# PHY.net
KiCad netlist of a schematic drawn in Altium Designer
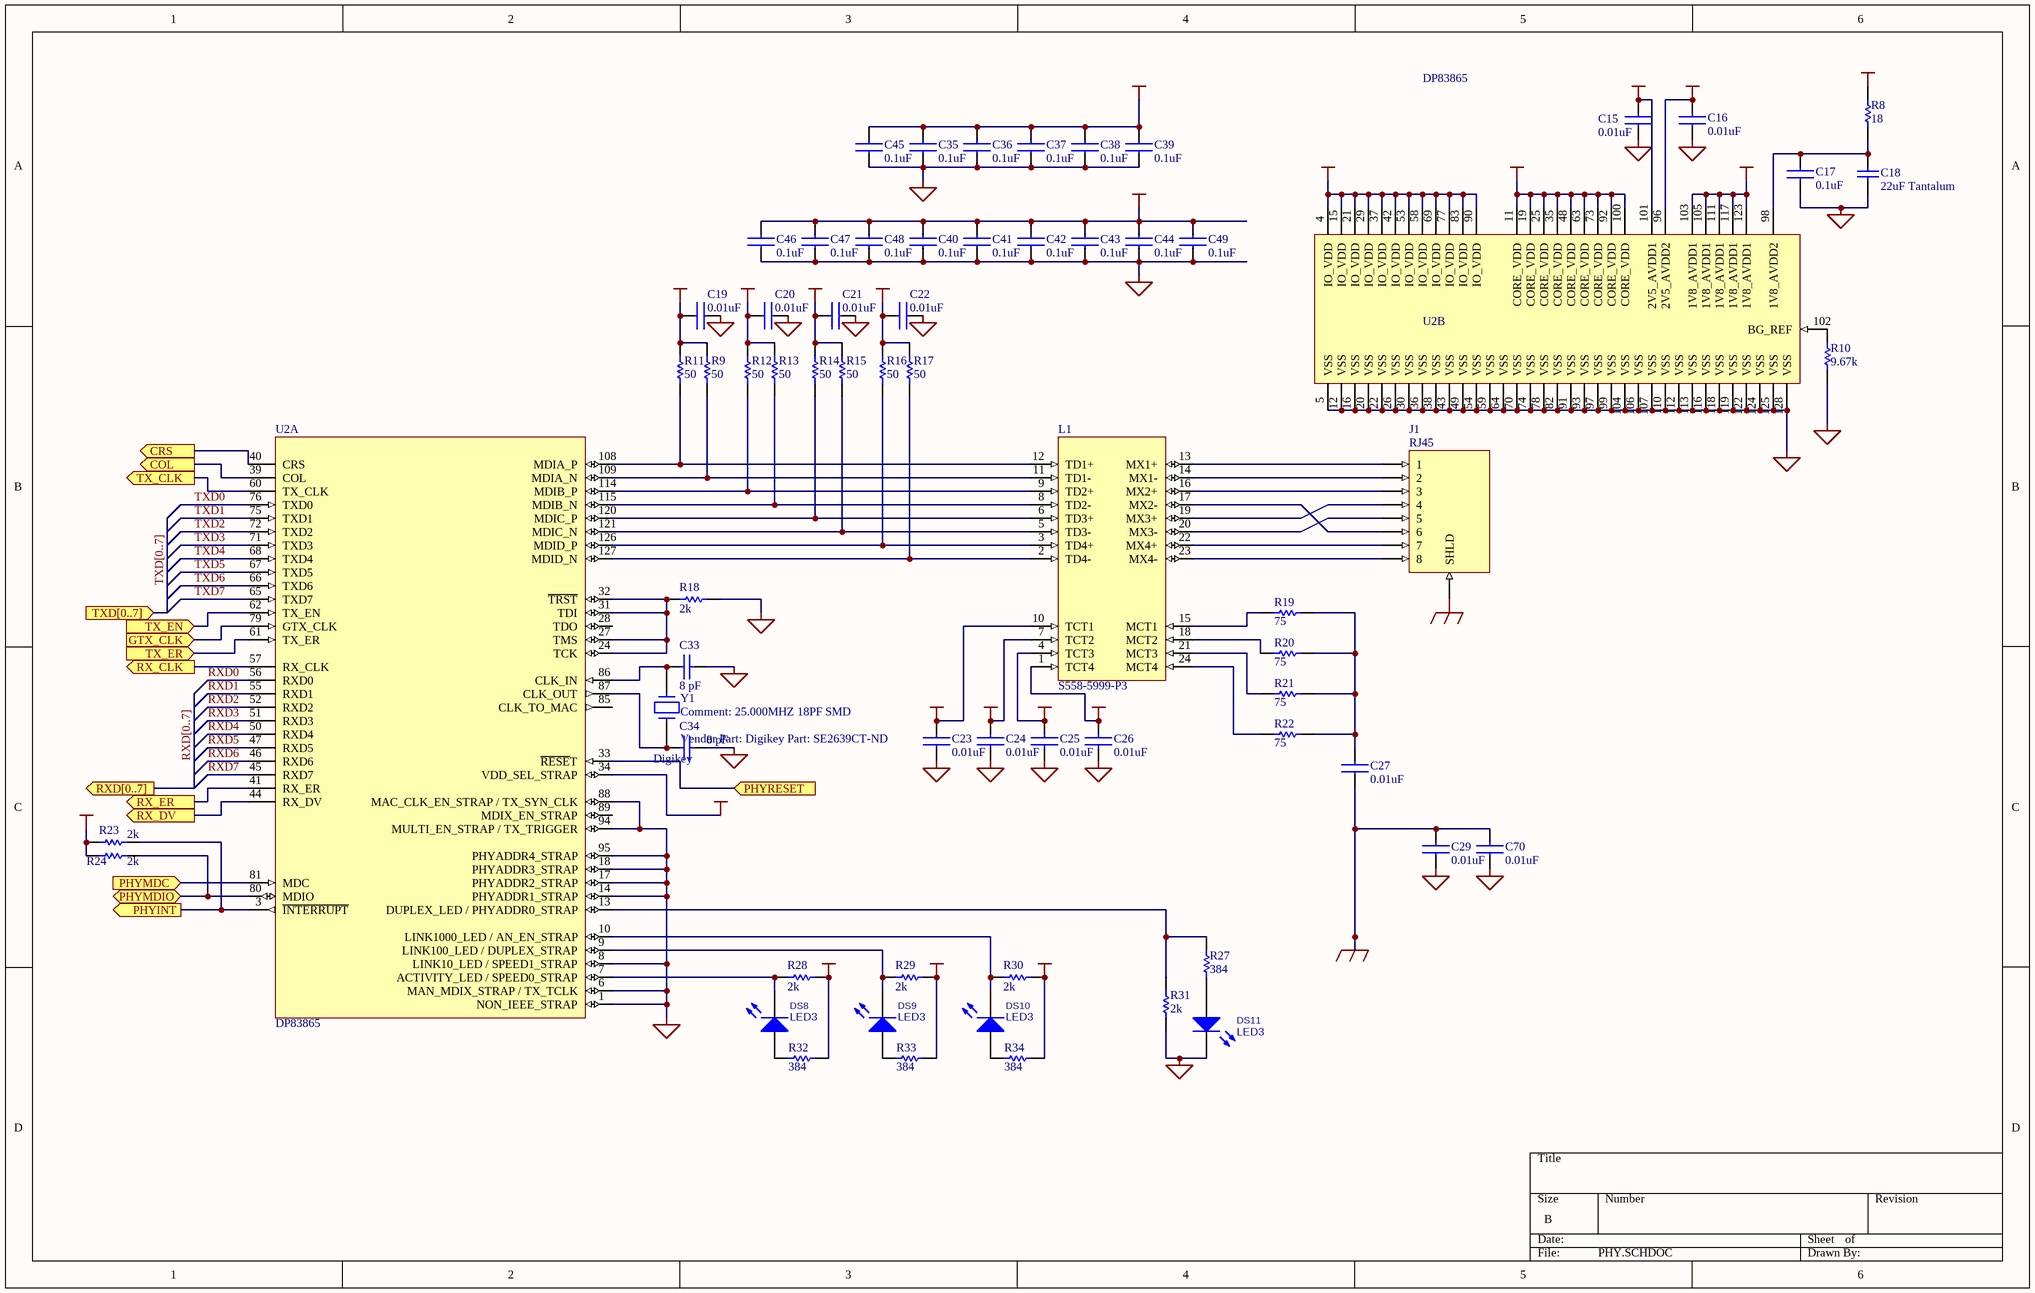
[diagram p0: PHY.SCHDOC]

(export (version "E")
  (design (tool "Eeschema 10.0.6"))
  (components
    (comp (ref "C15")
      (value "0.01uF")
      (footprint "0402")
      (description "Standard Capacitor")
      (fields (field (name "Comment") "CAPACITOR"))
      (libsource (lib "parts") (part "CAPACITOR"))
    )
    (comp (ref "C16")
      (value "0.01uF")
      (footprint "0402")
      (description "Standard Capacitor")
      (fields (field (name "Comment") "CAPACITOR"))
      (libsource (lib "parts") (part "CAPACITOR"))
    )
    (comp (ref "C17")
      (value "0.1uF")
      (footprint "0603")
      (description "Standard Capacitor")
      (fields (field (name "Comment") "CAPACITOR"))
      (libsource (lib "parts") (part "CAPACITOR"))
    )
    (comp (ref "C18")
      (value "22uF Tantalum")
      (footprint "TC7343-2917")
      (description "Capacitor")
      (fields
        (field (name "MANUFACTURER") "Generic Components")
        (field (name "Comment") "Cap")
        (field (name "PUBLISHER") "Altium Limited")
      )
      (libsource (lib "Miscellaneous Devices") (part "Cap"))
    )
    (comp (ref "C19")
      (value "0.01uF")
      (footprint "0402")
      (description "Standard Capacitor")
      (fields (field (name "Comment") "CAPACITOR"))
      (libsource (lib "parts") (part "CAPACITOR"))
    )
    (comp (ref "C20")
      (value "0.01uF")
      (footprint "0402")
      (description "Standard Capacitor")
      (fields (field (name "Comment") "CAPACITOR"))
      (libsource (lib "parts") (part "CAPACITOR"))
    )
    (comp (ref "C21")
      (value "0.01uF")
      (footprint "0402")
      (description "Standard Capacitor")
      (fields (field (name "Comment") "CAPACITOR"))
      (libsource (lib "parts") (part "CAPACITOR"))
    )
    (comp (ref "C22")
      (value "0.01uF")
      (footprint "0402")
      (description "Standard Capacitor")
      (fields (field (name "Comment") "CAPACITOR"))
      (libsource (lib "parts") (part "CAPACITOR"))
    )
    (comp (ref "C23")
      (value "0.01uF")
      (footprint "0402")
      (description "Standard Capacitor")
      (fields (field (name "Comment") "CAPACITOR"))
      (libsource (lib "parts") (part "CAPACITOR"))
    )
    (comp (ref "C24")
      (value "0.01uF")
      (footprint "0402")
      (description "Standard Capacitor")
      (fields (field (name "Comment") "CAPACITOR"))
      (libsource (lib "parts") (part "CAPACITOR"))
    )
    (comp (ref "C25")
      (value "0.01uF")
      (footprint "0402")
      (description "Standard Capacitor")
      (fields (field (name "Comment") "CAPACITOR"))
      (libsource (lib "parts") (part "CAPACITOR"))
    )
    (comp (ref "C26")
      (value "0.01uF")
      (footprint "0402")
      (description "Standard Capacitor")
      (fields (field (name "Comment") "CAPACITOR"))
      (libsource (lib "parts") (part "CAPACITOR"))
    )
    (comp (ref "C27")
      (value "0.01uF")
      (footprint "0402")
      (description "Standard Capacitor")
      (fields (field (name "Comment") "CAPACITOR"))
      (libsource (lib "parts") (part "CAPACITOR"))
    )
    (comp (ref "C29")
      (value "0.01uF")
      (footprint "0402")
      (description "Standard Capacitor")
      (fields (field (name "Comment") "CAPACITOR"))
      (libsource (lib "parts") (part "CAPACITOR"))
    )
    (comp (ref "C33")
      (value "8 pF")
      (footprint "0603")
      (description "Capacitor")
      (libsource (lib "*") (part "CAP"))
    )
    (comp (ref "C34")
      (value "8 pF")
      (footprint "0603")
      (description "Capacitor")
      (libsource (lib "*") (part "CAP"))
    )
    (comp (ref "C35")
      (value "0.1uF")
      (footprint "0603")
      (description "Standard Capacitor")
      (fields (field (name "Comment") "CAPACITOR"))
      (libsource (lib "parts") (part "CAPACITOR"))
    )
    (comp (ref "C36")
      (value "0.1uF")
      (footprint "0603")
      (description "Standard Capacitor")
      (fields (field (name "Comment") "CAPACITOR"))
      (libsource (lib "parts") (part "CAPACITOR"))
    )
    (comp (ref "C37")
      (value "0.1uF")
      (footprint "0603")
      (description "Standard Capacitor")
      (fields (field (name "Comment") "CAPACITOR"))
      (libsource (lib "parts") (part "CAPACITOR"))
    )
    (comp (ref "C38")
      (value "0.1uF")
      (footprint "0603")
      (description "Standard Capacitor")
      (fields (field (name "Comment") "CAPACITOR"))
      (libsource (lib "parts") (part "CAPACITOR"))
    )
    (comp (ref "C39")
      (value "0.1uF")
      (footprint "0603")
      (description "Standard Capacitor")
      (fields (field (name "Comment") "CAPACITOR"))
      (libsource (lib "parts") (part "CAPACITOR"))
    )
    (comp (ref "C40")
      (value "0.1uF")
      (footprint "0603")
      (description "Standard Capacitor")
      (fields (field (name "Comment") "CAPACITOR"))
      (libsource (lib "parts") (part "CAPACITOR"))
    )
    (comp (ref "C41")
      (value "0.1uF")
      (footprint "0603")
      (description "Standard Capacitor")
      (fields (field (name "Comment") "CAPACITOR"))
      (libsource (lib "parts") (part "CAPACITOR"))
    )
    (comp (ref "C42")
      (value "0.1uF")
      (footprint "0603")
      (description "Standard Capacitor")
      (fields (field (name "Comment") "CAPACITOR"))
      (libsource (lib "parts") (part "CAPACITOR"))
    )
    (comp (ref "C43")
      (value "0.1uF")
      (footprint "0603")
      (description "Standard Capacitor")
      (fields (field (name "Comment") "CAPACITOR"))
      (libsource (lib "parts") (part "CAPACITOR"))
    )
    (comp (ref "C44")
      (value "0.1uF")
      (footprint "0603")
      (description "Standard Capacitor")
      (fields (field (name "Comment") "CAPACITOR"))
      (libsource (lib "parts") (part "CAPACITOR"))
    )
    (comp (ref "C45")
      (value "0.1uF")
      (footprint "0603")
      (description "Standard Capacitor")
      (fields (field (name "Comment") "CAPACITOR"))
      (libsource (lib "parts") (part "CAPACITOR"))
    )
    (comp (ref "C46")
      (value "0.1uF")
      (footprint "0603")
      (description "Standard Capacitor")
      (fields (field (name "Comment") "CAPACITOR"))
      (libsource (lib "parts") (part "CAPACITOR"))
    )
    (comp (ref "C47")
      (value "0.1uF")
      (footprint "0603")
      (description "Standard Capacitor")
      (fields (field (name "Comment") "CAPACITOR"))
      (libsource (lib "parts") (part "CAPACITOR"))
    )
    (comp (ref "C48")
      (value "0.1uF")
      (footprint "0603")
      (description "Standard Capacitor")
      (fields (field (name "Comment") "CAPACITOR"))
      (libsource (lib "parts") (part "CAPACITOR"))
    )
    (comp (ref "C49")
      (value "0.1uF")
      (footprint "0603")
      (description "Standard Capacitor")
      (fields (field (name "Comment") "CAPACITOR"))
      (libsource (lib "parts") (part "CAPACITOR"))
    )
    (comp (ref "C70")
      (value "0.01uF")
      (footprint "0402")
      (description "Standard Capacitor")
      (fields (field (name "Comment") "CAPACITOR"))
      (libsource (lib "parts") (part "CAPACITOR"))
    )
    (comp (ref "DS8")
      (value "LED3")
      (footprint "SMD _LED")
      (description "Typical BLUE SiC LED")
      (fields (field (name "PUBLISHER") "Altium Limited"))
      (libsource (lib "Miscellaneous Devices") (part "LED3"))
    )
    (comp (ref "DS9")
      (value "LED3")
      (footprint "SMD _LED")
      (description "Typical BLUE SiC LED")
      (fields (field (name "PUBLISHER") "Altium Limited"))
      (libsource (lib "Miscellaneous Devices") (part "LED3"))
    )
    (comp (ref "DS10")
      (value "LED3")
      (footprint "SMD _LED")
      (description "Typical BLUE SiC LED")
      (fields (field (name "PUBLISHER") "Altium Limited"))
      (libsource (lib "Miscellaneous Devices") (part "LED3"))
    )
    (comp (ref "DS11")
      (value "LED3")
      (footprint "SMD _LED")
      (description "Typical BLUE SiC LED")
      (fields (field (name "PUBLISHER") "Altium Limited"))
      (libsource (lib "Miscellaneous Devices") (part "LED3"))
    )
    (comp (ref "J1")
      (value "RJ45")
      (footprint "MOLEXRJ45_44050-0007")
      (description "RJ-45 connector")
      (libsource (lib "*") (part "RJ45"))
    )
    (comp (ref "L1")
      (value "S558-5999-P3")
      (footprint "S558-5999-P3")
      (description "BEL 1000base-T magnetics S588-5999-P3")
      (libsource (lib "My devices") (part "S558-5999-P3"))
    )
    (comp (ref "R8")
      (value "18")
      (footprint "0603")
      (description "Resistor")
      (fields
        (field (name "MANUFACTURER") "Generic Components")
        (field (name "Comment") "Res1")
        (field (name "PUBLISHER") "Altium Limited")
      )
      (libsource (lib "Miscellaneous Devices") (part "Res1"))
    )
    (comp (ref "R9")
      (value "50")
      (footprint "0603")
      (description "Standard Passive Resistor")
      (fields (field (name "Comment") "RESISTOR"))
      (libsource (lib "parts") (part "RESISTOR"))
    )
    (comp (ref "R10")
      (value "9.67k")
      (footprint "0603")
      (description "Resistor")
      (fields
        (field (name "MANUFACTURER") "Generic Components")
        (field (name "Comment") "Res1")
        (field (name "PUBLISHER") "Altium Limited")
      )
      (libsource (lib "Miscellaneous Devices") (part "Res1"))
    )
    (comp (ref "R11")
      (value "50")
      (footprint "0603")
      (description "Standard Passive Resistor")
      (fields (field (name "Comment") "RESISTOR"))
      (libsource (lib "parts") (part "RESISTOR"))
    )
    (comp (ref "R12")
      (value "50")
      (footprint "0603")
      (description "Standard Passive Resistor")
      (fields (field (name "Comment") "RESISTOR"))
      (libsource (lib "parts") (part "RESISTOR"))
    )
    (comp (ref "R13")
      (value "50")
      (footprint "0603")
      (description "Standard Passive Resistor")
      (fields (field (name "Comment") "RESISTOR"))
      (libsource (lib "parts") (part "RESISTOR"))
    )
    (comp (ref "R14")
      (value "50")
      (footprint "0603")
      (description "Standard Passive Resistor")
      (fields (field (name "Comment") "RESISTOR"))
      (libsource (lib "parts") (part "RESISTOR"))
    )
    (comp (ref "R15")
      (value "50")
      (footprint "0603")
      (description "Standard Passive Resistor")
      (fields (field (name "Comment") "RESISTOR"))
      (libsource (lib "parts") (part "RESISTOR"))
    )
    (comp (ref "R16")
      (value "50")
      (footprint "0603")
      (description "Standard Passive Resistor")
      (fields (field (name "Comment") "RESISTOR"))
      (libsource (lib "parts") (part "RESISTOR"))
    )
    (comp (ref "R17")
      (value "50")
      (footprint "0603")
      (description "Standard Passive Resistor")
      (fields (field (name "Comment") "RESISTOR"))
      (libsource (lib "parts") (part "RESISTOR"))
    )
    (comp (ref "R18")
      (value "2k")
      (footprint "0603")
      (description "Standard Passive Resistor")
      (fields (field (name "Comment") "RESISTOR"))
      (libsource (lib "parts") (part "RESISTOR"))
    )
    (comp (ref "R19")
      (value "75")
      (footprint "0603")
      (description "Resistor")
      (fields
        (field (name "MANUFACTURER") "Generic Components")
        (field (name "Comment") "Res1")
        (field (name "PUBLISHER") "Altium Limited")
      )
      (libsource (lib "Miscellaneous Devices") (part "Res1"))
    )
    (comp (ref "R20")
      (value "75")
      (footprint "0603")
      (description "Resistor")
      (fields
        (field (name "MANUFACTURER") "Generic Components")
        (field (name "Comment") "Res1")
        (field (name "PUBLISHER") "Altium Limited")
      )
      (libsource (lib "Miscellaneous Devices") (part "Res1"))
    )
    (comp (ref "R21")
      (value "75")
      (footprint "0603")
      (description "Resistor")
      (fields
        (field (name "MANUFACTURER") "Generic Components")
        (field (name "Comment") "Res1")
        (field (name "PUBLISHER") "Altium Limited")
      )
      (libsource (lib "Miscellaneous Devices") (part "Res1"))
    )
    (comp (ref "R22")
      (value "75")
      (footprint "0603")
      (description "Resistor")
      (fields
        (field (name "MANUFACTURER") "Generic Components")
        (field (name "Comment") "Res1")
        (field (name "PUBLISHER") "Altium Limited")
      )
      (libsource (lib "Miscellaneous Devices") (part "Res1"))
    )
    (comp (ref "R23")
      (value "2k")
      (footprint "0603")
      (description "Standard Passive Resistor")
      (fields (field (name "Comment") "RESISTOR"))
      (libsource (lib "parts") (part "RESISTOR"))
    )
    (comp (ref "R24")
      (value "2k")
      (footprint "0603")
      (description "Standard Passive Resistor")
      (fields (field (name "Comment") "RESISTOR"))
      (libsource (lib "parts") (part "RESISTOR"))
    )
    (comp (ref "R27")
      (value "384")
      (footprint "0603")
      (description "Resistor")
      (fields
        (field (name "MANUFACTURER") "Generic Components")
        (field (name "Comment") "Res1")
        (field (name "PUBLISHER") "Altium Limited")
      )
      (libsource (lib "Miscellaneous Devices") (part "Res1"))
    )
    (comp (ref "R28")
      (value "2k")
      (footprint "0603")
      (description "Standard Passive Resistor")
      (fields (field (name "Comment") "RESISTOR"))
      (libsource (lib "parts") (part "RESISTOR"))
    )
    (comp (ref "R29")
      (value "2k")
      (footprint "0603")
      (description "Standard Passive Resistor")
      (fields (field (name "Comment") "RESISTOR"))
      (libsource (lib "parts") (part "RESISTOR"))
    )
    (comp (ref "R30")
      (value "2k")
      (footprint "0603")
      (description "Standard Passive Resistor")
      (fields (field (name "Comment") "RESISTOR"))
      (libsource (lib "parts") (part "RESISTOR"))
    )
    (comp (ref "R31")
      (value "2k")
      (footprint "0603")
      (description "Standard Passive Resistor")
      (fields (field (name "Comment") "RESISTOR"))
      (libsource (lib "parts") (part "RESISTOR"))
    )
    (comp (ref "R32")
      (value "384")
      (footprint "0603")
      (description "Resistor")
      (fields
        (field (name "MANUFACTURER") "Generic Components")
        (field (name "Comment") "Res1")
        (field (name "PUBLISHER") "Altium Limited")
      )
      (libsource (lib "Miscellaneous Devices") (part "Res1"))
    )
    (comp (ref "R33")
      (value "384")
      (footprint "0603")
      (description "Resistor")
      (fields
        (field (name "MANUFACTURER") "Generic Components")
        (field (name "Comment") "Res1")
        (field (name "PUBLISHER") "Altium Limited")
      )
      (libsource (lib "Miscellaneous Devices") (part "Res1"))
    )
    (comp (ref "R34")
      (value "384")
      (footprint "0603")
      (description "Resistor")
      (fields
        (field (name "MANUFACTURER") "Generic Components")
        (field (name "Comment") "Res1")
        (field (name "PUBLISHER") "Altium Limited")
      )
      (libsource (lib "Miscellaneous Devices") (part "Res1"))
    )
    (comp (ref "U2")
      (value "DP83865")
      (footprint "PQFP128RECT")
      (description "National Semiconductor Gigabit PHY")
      (libsource (lib "My devices") (part "DP83865"))
    )
    (comp (ref "Y1")
      (value "25.000MHZ 18PF SMD")
      (footprint "EPSON_MA-506")
      (description "Crystal MA-506 25.000M-C0")
      (fields (field (name "VENDOR PART") "Digikey Part: SE2639CT-ND") (field (name "VENDOR") "Digikey"))
      (libsource (lib "*") (part "CRYSTAL"))
    )
  )
  (nets
    (net (code "1") (name "+1.8VCC") (class "Default")
      (node (ref "C40") (pin "1") (pintype "passive"))
      (node (ref "C41") (pin "1") (pintype "passive"))
      (node (ref "C42") (pin "1") (pintype "passive"))
      (node (ref "C43") (pin "1") (pintype "passive"))
      (node (ref "C44") (pin "1") (pintype "passive"))
      (node (ref "C46") (pin "1") (pintype "passive"))
      (node (ref "C47") (pin "1") (pintype "passive"))
      (node (ref "C48") (pin "1") (pintype "passive"))
      (node (ref "C49") (pin "1") (pintype "passive"))
      (node (ref "R8") (pin "2") (pinfunction "2_2") (pintype "passive"))
      (node (ref "U2") (pin "100") (pinfunction "CORE_VDD_100") (pintype "power_in"))
      (node (ref "U2") (pin "103") (pinfunction "1V8_AVDD1_103") (pintype "power_in"))
      (node (ref "U2") (pin "105") (pinfunction "1V8_AVDD1_105") (pintype "power_in"))
      (node (ref "U2") (pin "11") (pinfunction "CORE_VDD_11") (pintype "power_in"))
      (node (ref "U2") (pin "111") (pinfunction "1V8_AVDD1_111") (pintype "power_in"))
      (node (ref "U2") (pin "117") (pinfunction "1V8_AVDD1_117") (pintype "power_in"))
      (node (ref "U2") (pin "123") (pinfunction "1V8_AVDD1_123") (pintype "power_in"))
      (node (ref "U2") (pin "19") (pinfunction "CORE_VDD_19") (pintype "power_in"))
      (node (ref "U2") (pin "25") (pinfunction "CORE_VDD_25") (pintype "power_in"))
      (node (ref "U2") (pin "35") (pinfunction "CORE_VDD_35") (pintype "power_in"))
      (node (ref "U2") (pin "48") (pinfunction "CORE_VDD_48") (pintype "power_in"))
      (node (ref "U2") (pin "63") (pinfunction "CORE_VDD_63") (pintype "power_in"))
      (node (ref "U2") (pin "73") (pinfunction "CORE_VDD_73") (pintype "power_in"))
      (node (ref "U2") (pin "92") (pinfunction "CORE_VDD_92") (pintype "power_in"))
    )
    (net (code "2") (name "+2.5VPHY") (class "Default")
      (node (ref "C15") (pin "2") (pintype "passive"))
      (node (ref "C16") (pin "2") (pintype "passive"))
      (node (ref "C19") (pin "1") (pintype "passive"))
      (node (ref "C20") (pin "1") (pintype "passive"))
      (node (ref "C21") (pin "1") (pintype "passive"))
      (node (ref "C22") (pin "1") (pintype "passive"))
      (node (ref "C23") (pin "2") (pintype "passive"))
      (node (ref "C24") (pin "2") (pintype "passive"))
      (node (ref "C25") (pin "2") (pintype "passive"))
      (node (ref "C26") (pin "2") (pintype "passive"))
      (node (ref "L1") (pin "1") (pinfunction "TCT4_1") (pintype "input"))
      (node (ref "L1") (pin "10") (pinfunction "TCT1_10") (pintype "input"))
      (node (ref "L1") (pin "4") (pinfunction "TCT3_4") (pintype "input"))
      (node (ref "L1") (pin "7") (pinfunction "TCT2_7") (pintype "input"))
      (node (ref "R11") (pin "2") (pintype "passive"))
      (node (ref "R12") (pin "2") (pintype "passive"))
      (node (ref "R13") (pin "2") (pintype "passive"))
      (node (ref "R14") (pin "2") (pintype "passive"))
      (node (ref "R15") (pin "2") (pintype "passive"))
      (node (ref "R16") (pin "2") (pintype "passive"))
      (node (ref "R17") (pin "2") (pintype "passive"))
      (node (ref "R9") (pin "2") (pintype "passive"))
      (node (ref "U2") (pin "101") (pinfunction "2V5_AVDD1_101") (pintype "power_in"))
      (node (ref "U2") (pin "96") (pinfunction "2V5_AVDD2_96") (pintype "power_in"))
    )
    (net (code "3") (name "/COL") (class "Default")
      (node (ref "U2") (pin "39") (pinfunction "COL_39") (pintype "tri_state"))
    )
    (net (code "4") (name "/CRS") (class "Default")
      (node (ref "U2") (pin "40") (pinfunction "CRS_40") (pintype "tri_state"))
    )
    (net (code "5") (name "/GTX_CLK") (class "Default")
      (node (ref "U2") (pin "79") (pinfunction "GTX_CLK_79") (pintype "input"))
    )
    (net (code "6") (name "/PHYINT") (class "Default")
      (node (ref "R23") (pin "2") (pintype "passive"))
      (node (ref "U2") (pin "3") (pinfunction "~{INTERRUPT}_3") (pintype "output"))
    )
    (net (code "7") (name "/PHYMDC") (class "Default")
      (node (ref "U2") (pin "81") (pinfunction "MDC_81") (pintype "input"))
    )
    (net (code "8") (name "/PHYMDIO") (class "Default")
      (node (ref "R24") (pin "2") (pintype "passive"))
      (node (ref "U2") (pin "80") (pinfunction "MDIO_80") (pintype "bidirectional"))
    )
    (net (code "9") (name "/PHYRESET") (class "Default")
      (node (ref "U2") (pin "33") (pinfunction "~{RESE}T_33") (pintype "input"))
    )
    (net (code "10") (name "/RXD0") (class "Default")
      (node (ref "U2") (pin "56") (pinfunction "RXD0_56") (pintype "tri_state"))
    )
    (net (code "11") (name "/RXD1") (class "Default")
      (node (ref "U2") (pin "55") (pinfunction "RXD1_55") (pintype "tri_state"))
    )
    (net (code "12") (name "/RXD2") (class "Default")
      (node (ref "U2") (pin "52") (pinfunction "RXD2_52") (pintype "tri_state"))
    )
    (net (code "13") (name "/RXD3") (class "Default")
      (node (ref "U2") (pin "51") (pinfunction "RXD3_51") (pintype "tri_state"))
    )
    (net (code "14") (name "/RXD4") (class "Default")
      (node (ref "U2") (pin "50") (pinfunction "RXD4_50") (pintype "tri_state"))
    )
    (net (code "15") (name "/RXD5") (class "Default")
      (node (ref "U2") (pin "47") (pinfunction "RXD5_47") (pintype "tri_state"))
    )
    (net (code "16") (name "/RXD6") (class "Default")
      (node (ref "U2") (pin "46") (pinfunction "RXD6_46") (pintype "tri_state"))
    )
    (net (code "17") (name "/RXD7") (class "Default")
      (node (ref "U2") (pin "45") (pinfunction "RXD7_45") (pintype "tri_state"))
    )
    (net (code "19") (name "/RX_CLK") (class "Default")
      (node (ref "U2") (pin "57") (pinfunction "RX_CLK_57") (pintype "tri_state"))
    )
    (net (code "20") (name "/RX_DV") (class "Default")
      (node (ref "U2") (pin "44") (pinfunction "RX_DV_44") (pintype "tri_state"))
    )
    (net (code "21") (name "/RX_ER") (class "Default")
      (node (ref "U2") (pin "41") (pinfunction "RX_ER_41") (pintype "tri_state"))
    )
    (net (code "22") (name "/TXD0") (class "Default")
      (node (ref "U2") (pin "76") (pinfunction "TXD0_76") (pintype "input"))
    )
    (net (code "23") (name "/TXD1") (class "Default")
      (node (ref "U2") (pin "75") (pinfunction "TXD1_75") (pintype "input"))
    )
    (net (code "24") (name "/TXD2") (class "Default")
      (node (ref "U2") (pin "72") (pinfunction "TXD2_72") (pintype "input"))
    )
    (net (code "25") (name "/TXD3") (class "Default")
      (node (ref "U2") (pin "71") (pinfunction "TXD3_71") (pintype "input"))
    )
    (net (code "26") (name "/TXD4") (class "Default")
      (node (ref "U2") (pin "68") (pinfunction "TXD4_68") (pintype "input"))
    )
    (net (code "27") (name "/TXD5") (class "Default")
      (node (ref "U2") (pin "67") (pinfunction "TXD5_67") (pintype "input"))
    )
    (net (code "28") (name "/TXD6") (class "Default")
      (node (ref "U2") (pin "66") (pinfunction "TXD6_66") (pintype "input"))
    )
    (net (code "29") (name "/TXD7") (class "Default")
      (node (ref "U2") (pin "65") (pinfunction "TXD7_65") (pintype "input"))
    )
    (net (code "31") (name "/TX_CLK") (class "Default")
      (node (ref "U2") (pin "60") (pinfunction "TX_CLK_60") (pintype "tri_state"))
    )
    (net (code "32") (name "/TX_EN") (class "Default")
      (node (ref "U2") (pin "62") (pinfunction "TX_EN_62") (pintype "input"))
    )
    (net (code "33") (name "/TX_ER") (class "Default")
      (node (ref "U2") (pin "61") (pinfunction "TX_ER_61") (pintype "input"))
    )
    (net (code "34") (name "CGND") (class "Default")
      (node (ref "C27") (pin "1") (pintype "passive"))
      (node (ref "C29") (pin "2") (pintype "passive"))
      (node (ref "C70") (pin "2") (pintype "passive"))
      (node (ref "J1") (pin "9") (pinfunction "SHLD_9") (pintype "input"))
    )
    (net (code "35") (name "GND") (class "Default")
      (node (ref "C15") (pin "1") (pintype "passive"))
      (node (ref "C16") (pin "1") (pintype "passive"))
      (node (ref "C17") (pin "1") (pintype "passive"))
      (node (ref "C18") (pin "1") (pinfunction "1_1") (pintype "passive"))
      (node (ref "C19") (pin "2") (pintype "passive"))
      (node (ref "C20") (pin "2") (pintype "passive"))
      (node (ref "C21") (pin "2") (pintype "passive"))
      (node (ref "C22") (pin "2") (pintype "passive"))
      (node (ref "C23") (pin "1") (pintype "passive"))
      (node (ref "C24") (pin "1") (pintype "passive"))
      (node (ref "C25") (pin "1") (pintype "passive"))
      (node (ref "C26") (pin "1") (pintype "passive"))
      (node (ref "C29") (pin "1") (pintype "passive"))
      (node (ref "C33") (pin "2") (pinfunction "2_2") (pintype "passive"))
      (node (ref "C34") (pin "2") (pinfunction "2_2") (pintype "passive"))
      (node (ref "C35") (pin "2") (pintype "passive"))
      (node (ref "C36") (pin "2") (pintype "passive"))
      (node (ref "C37") (pin "2") (pintype "passive"))
      (node (ref "C38") (pin "2") (pintype "passive"))
      (node (ref "C39") (pin "2") (pintype "passive"))
      (node (ref "C40") (pin "2") (pintype "passive"))
      (node (ref "C41") (pin "2") (pintype "passive"))
      (node (ref "C42") (pin "2") (pintype "passive"))
      (node (ref "C43") (pin "2") (pintype "passive"))
      (node (ref "C44") (pin "2") (pintype "passive"))
      (node (ref "C45") (pin "2") (pintype "passive"))
      (node (ref "C46") (pin "2") (pintype "passive"))
      (node (ref "C47") (pin "2") (pintype "passive"))
      (node (ref "C48") (pin "2") (pintype "passive"))
      (node (ref "C49") (pin "2") (pintype "passive"))
      (node (ref "C70") (pin "1") (pintype "passive"))
      (node (ref "DS11") (pin "2") (pinfunction "K_2") (pintype "passive"))
      (node (ref "R10") (pin "1") (pinfunction "1_1") (pintype "passive"))
      (node (ref "R18") (pin "2") (pintype "passive"))
      (node (ref "R31") (pin "1") (pintype "passive"))
      (node (ref "U2") (pin "1") (pinfunction "NON_IEEE_STRAP_1") (pintype "bidirectional"))
      (node (ref "U2") (pin "104") (pinfunction "VSS_104") (pintype "power_in"))
      (node (ref "U2") (pin "106") (pinfunction "VSS_106") (pintype "power_in"))
      (node (ref "U2") (pin "107") (pinfunction "VSS_107") (pintype "power_in"))
      (node (ref "U2") (pin "110") (pinfunction "VSS_110") (pintype "power_in"))
      (node (ref "U2") (pin "112") (pinfunction "VSS_112") (pintype "power_in"))
      (node (ref "U2") (pin "113") (pinfunction "VSS_113") (pintype "power_in"))
      (node (ref "U2") (pin "116") (pinfunction "VSS_116") (pintype "power_in"))
      (node (ref "U2") (pin "118") (pinfunction "VSS_118") (pintype "power_in"))
      (node (ref "U2") (pin "119") (pinfunction "VSS_119") (pintype "power_in"))
      (node (ref "U2") (pin "12") (pinfunction "VSS_12") (pintype "power_in"))
      (node (ref "U2") (pin "122") (pinfunction "VSS_122") (pintype "power_in"))
      (node (ref "U2") (pin "124") (pinfunction "VSS_124") (pintype "power_in"))
      (node (ref "U2") (pin "125") (pinfunction "VSS_125") (pintype "power_in"))
      (node (ref "U2") (pin "128") (pinfunction "VSS_128") (pintype "power_in"))
      (node (ref "U2") (pin "14") (pinfunction "PHYADDR1_STRAP_14") (pintype "bidirectional"))
      (node (ref "U2") (pin "16") (pinfunction "VSS_16") (pintype "power_in"))
      (node (ref "U2") (pin "17") (pinfunction "PHYADDR2_STRAP_17") (pintype "bidirectional"))
      (node (ref "U2") (pin "18") (pinfunction "PHYADDR3_STRAP_18") (pintype "bidirectional"))
      (node (ref "U2") (pin "20") (pinfunction "VSS_20") (pintype "power_in"))
      (node (ref "U2") (pin "22") (pinfunction "VSS_22") (pintype "power_in"))
      (node (ref "U2") (pin "26") (pinfunction "VSS_26") (pintype "power_in"))
      (node (ref "U2") (pin "30") (pinfunction "VSS_30") (pintype "power_in"))
      (node (ref "U2") (pin "36") (pinfunction "VSS_36") (pintype "power_in"))
      (node (ref "U2") (pin "38") (pinfunction "VSS_38") (pintype "power_in"))
      (node (ref "U2") (pin "43") (pinfunction "VSS_43") (pintype "power_in"))
      (node (ref "U2") (pin "49") (pinfunction "VSS_49") (pintype "power_in"))
      (node (ref "U2") (pin "5") (pinfunction "VSS_5") (pintype "power_in"))
      (node (ref "U2") (pin "54") (pinfunction "VSS_54") (pintype "power_in"))
      (node (ref "U2") (pin "59") (pinfunction "VSS_59") (pintype "power_in"))
      (node (ref "U2") (pin "6") (pinfunction "MAN_MDIX_STRAP_/_TX_TCLK_6") (pintype "bidirectional"))
      (node (ref "U2") (pin "64") (pinfunction "VSS_64") (pintype "power_in"))
      (node (ref "U2") (pin "70") (pinfunction "VSS_70") (pintype "power_in"))
      (node (ref "U2") (pin "74") (pinfunction "VSS_74") (pintype "power_in"))
      (node (ref "U2") (pin "78") (pinfunction "VSS_78") (pintype "power_in"))
      (node (ref "U2") (pin "8") (pinfunction "LINK10_LED_/_SPEED1_STRAP_8") (pintype "bidirectional"))
      (node (ref "U2") (pin "82") (pinfunction "VSS_82") (pintype "power_in"))
      (node (ref "U2") (pin "88") (pinfunction "MAC_CLK_EN_STRAP_/_TX_SYN_CLK_88") (pintype "bidirectional"))
      (node (ref "U2") (pin "91") (pinfunction "VSS_91") (pintype "power_in"))
      (node (ref "U2") (pin "93") (pinfunction "VSS_93") (pintype "power_in"))
      (node (ref "U2") (pin "94") (pinfunction "MULTI_EN_STRAP_/_TX_TRIGGER_94") (pintype "bidirectional"))
      (node (ref "U2") (pin "95") (pinfunction "PHYADDR4_STRAP_95") (pintype "bidirectional"))
      (node (ref "U2") (pin "97") (pinfunction "VSS_97") (pintype "power_in"))
      (node (ref "U2") (pin "99") (pinfunction "VSS_99") (pintype "power_in"))
    )
    (net (code "36") (name "Net-(C27-Pad2)") (class "Default")
      (node (ref "C27") (pin "2") (pintype "passive"))
      (node (ref "R19") (pin "1") (pinfunction "1_1") (pintype "passive"))
      (node (ref "R20") (pin "1") (pinfunction "1_1") (pintype "passive"))
      (node (ref "R21") (pin "1") (pinfunction "1_1") (pintype "passive"))
      (node (ref "R22") (pin "1") (pinfunction "1_1") (pintype "passive"))
    )
    (net (code "37") (name "Net-(DS8-A)") (class "Default")
      (node (ref "DS8") (pin "1") (pinfunction "A_1") (pintype "passive"))
      (node (ref "R32") (pin "1") (pinfunction "1_1") (pintype "passive"))
    )
    (net (code "38") (name "Net-(DS8-K)") (class "Default")
      (node (ref "DS8") (pin "2") (pinfunction "K_2") (pintype "passive"))
      (node (ref "R28") (pin "1") (pintype "passive"))
      (node (ref "U2") (pin "7") (pinfunction "ACTIVITY_LED_/_SPEED0_STRAP_7") (pintype "bidirectional"))
    )
    (net (code "39") (name "Net-(DS9-A)") (class "Default")
      (node (ref "DS9") (pin "1") (pinfunction "A_1") (pintype "passive"))
      (node (ref "R33") (pin "1") (pinfunction "1_1") (pintype "passive"))
    )
    (net (code "40") (name "Net-(DS9-K)") (class "Default")
      (node (ref "DS9") (pin "2") (pinfunction "K_2") (pintype "passive"))
      (node (ref "R29") (pin "1") (pintype "passive"))
      (node (ref "U2") (pin "9") (pinfunction "LINK100_LED_/_DUPLEX_STRAP_9") (pintype "bidirectional"))
    )
    (net (code "41") (name "Net-(DS10-A)") (class "Default")
      (node (ref "DS10") (pin "1") (pinfunction "A_1") (pintype "passive"))
      (node (ref "R34") (pin "1") (pinfunction "1_1") (pintype "passive"))
    )
    (net (code "42") (name "Net-(DS10-K)") (class "Default")
      (node (ref "DS10") (pin "2") (pinfunction "K_2") (pintype "passive"))
      (node (ref "R30") (pin "1") (pintype "passive"))
      (node (ref "U2") (pin "10") (pinfunction "LINK1000_LED_/_AN_EN_STRAP_10") (pintype "bidirectional"))
    )
    (net (code "43") (name "Net-(DS11-A)") (class "Default")
      (node (ref "DS11") (pin "1") (pinfunction "A_1") (pintype "passive"))
      (node (ref "R27") (pin "1") (pinfunction "1_1") (pintype "passive"))
    )
    (net (code "44") (name "Net-(L1-MCT1)") (class "Default")
      (node (ref "L1") (pin "15") (pinfunction "MCT1_15") (pintype "input"))
      (node (ref "R19") (pin "2") (pinfunction "2_2") (pintype "passive"))
    )
    (net (code "45") (name "Net-(L1-MCT2)") (class "Default")
      (node (ref "L1") (pin "18") (pinfunction "MCT2_18") (pintype "input"))
      (node (ref "R20") (pin "2") (pinfunction "2_2") (pintype "passive"))
    )
    (net (code "46") (name "Net-(L1-MCT3)") (class "Default")
      (node (ref "L1") (pin "21") (pinfunction "MCT3_21") (pintype "input"))
      (node (ref "R21") (pin "2") (pinfunction "2_2") (pintype "passive"))
    )
    (net (code "47") (name "Net-(L1-MCT4)") (class "Default")
      (node (ref "L1") (pin "24") (pinfunction "MCT4_24") (pintype "input"))
      (node (ref "R22") (pin "2") (pinfunction "2_2") (pintype "passive"))
    )
    (net (code "48") (name "Net-(L1-MX1+)") (class "Default")
      (node (ref "J1") (pin "1") (pinfunction "1_1") (pintype "input"))
      (node (ref "L1") (pin "13") (pinfunction "MX1+_13") (pintype "bidirectional"))
    )
    (net (code "49") (name "Net-(L1-MX1-)") (class "Default")
      (node (ref "J1") (pin "2") (pinfunction "2_2") (pintype "input"))
      (node (ref "L1") (pin "14") (pinfunction "MX1-_14") (pintype "bidirectional"))
    )
    (net (code "50") (name "Net-(L1-MX2+)") (class "Default")
      (node (ref "J1") (pin "3") (pinfunction "3_3") (pintype "input"))
      (node (ref "L1") (pin "16") (pinfunction "MX2+_16") (pintype "bidirectional"))
    )
    (net (code "51") (name "Net-(L1-MX2-)") (class "Default")
      (node (ref "J1") (pin "6") (pinfunction "6_6") (pintype "input"))
      (node (ref "L1") (pin "17") (pinfunction "MX2-_17") (pintype "bidirectional"))
    )
    (net (code "52") (name "Net-(L1-MX3+)") (class "Default")
      (node (ref "J1") (pin "4") (pinfunction "4_4") (pintype "input"))
      (node (ref "L1") (pin "19") (pinfunction "MX3+_19") (pintype "bidirectional"))
    )
    (net (code "53") (name "Net-(L1-MX3-)") (class "Default")
      (node (ref "J1") (pin "5") (pinfunction "5_5") (pintype "input"))
      (node (ref "L1") (pin "20") (pinfunction "MX3-_20") (pintype "bidirectional"))
    )
    (net (code "54") (name "Net-(L1-MX4+)") (class "Default")
      (node (ref "J1") (pin "7") (pinfunction "7_7") (pintype "input"))
      (node (ref "L1") (pin "22") (pinfunction "MX4+_22") (pintype "bidirectional"))
    )
    (net (code "55") (name "Net-(L1-MX4-)") (class "Default")
      (node (ref "J1") (pin "8") (pinfunction "8_8") (pintype "input"))
      (node (ref "L1") (pin "23") (pinfunction "MX4-_23") (pintype "bidirectional"))
    )
    (net (code "56") (name "Net-(L1-TD1+)") (class "Default")
      (node (ref "L1") (pin "12") (pinfunction "TD1+_12") (pintype "input"))
      (node (ref "R11") (pin "1") (pintype "passive"))
      (node (ref "U2") (pin "108") (pinfunction "MDIA_P_108") (pintype "bidirectional"))
    )
    (net (code "57") (name "Net-(L1-TD1-)") (class "Default")
      (node (ref "L1") (pin "11") (pinfunction "TD1-_11") (pintype "input"))
      (node (ref "R9") (pin "1") (pintype "passive"))
      (node (ref "U2") (pin "109") (pinfunction "MDIA_N_109") (pintype "bidirectional"))
    )
    (net (code "58") (name "Net-(L1-TD2+)") (class "Default")
      (node (ref "L1") (pin "9") (pinfunction "TD2+_9") (pintype "input"))
      (node (ref "R12") (pin "1") (pintype "passive"))
      (node (ref "U2") (pin "114") (pinfunction "MDIB_P_114") (pintype "bidirectional"))
    )
    (net (code "59") (name "Net-(L1-TD2-)") (class "Default")
      (node (ref "L1") (pin "8") (pinfunction "TD2-_8") (pintype "input"))
      (node (ref "R13") (pin "1") (pintype "passive"))
      (node (ref "U2") (pin "115") (pinfunction "MDIB_N_115") (pintype "bidirectional"))
    )
    (net (code "60") (name "Net-(L1-TD3+)") (class "Default")
      (node (ref "L1") (pin "6") (pinfunction "TD3+_6") (pintype "input"))
      (node (ref "R14") (pin "1") (pintype "passive"))
      (node (ref "U2") (pin "120") (pinfunction "MDIC_P_120") (pintype "bidirectional"))
    )
    (net (code "61") (name "Net-(L1-TD3-)") (class "Default")
      (node (ref "L1") (pin "5") (pinfunction "TD3-_5") (pintype "input"))
      (node (ref "R15") (pin "1") (pintype "passive"))
      (node (ref "U2") (pin "121") (pinfunction "MDIC_N_121") (pintype "bidirectional"))
    )
    (net (code "62") (name "Net-(L1-TD4+)") (class "Default")
      (node (ref "L1") (pin "3") (pinfunction "TD4+_3") (pintype "input"))
      (node (ref "R16") (pin "1") (pintype "passive"))
      (node (ref "U2") (pin "126") (pinfunction "MDID_P_126") (pintype "bidirectional"))
    )
    (net (code "63") (name "Net-(L1-TD4-)") (class "Default")
      (node (ref "L1") (pin "2") (pinfunction "TD4-_2") (pintype "input"))
      (node (ref "R17") (pin "1") (pintype "passive"))
      (node (ref "U2") (pin "127") (pinfunction "MDID_N_127") (pintype "bidirectional"))
    )
    (net (code "64") (name "Net-(U2A-CLK_IN)") (class "Default")
      (node (ref "C33") (pin "1") (pinfunction "1_1") (pintype "passive"))
      (node (ref "U2") (pin "86") (pinfunction "CLK_IN_86") (pintype "input"))
      (node (ref "Y1") (pin "1") (pinfunction "1_1") (pintype "passive"))
    )
    (net (code "65") (name "Net-(U2A-CLK_OUT)") (class "Default")
      (node (ref "C34") (pin "1") (pinfunction "1_1") (pintype "passive"))
      (node (ref "U2") (pin "87") (pinfunction "CLK_OUT_87") (pintype "output"))
      (node (ref "Y1") (pin "2") (pinfunction "2_2") (pintype "passive"))
    )
    (net (code "66") (name "Net-(U2A-DUPLEX_LED_{slash}_PHYADDR0_STRAP)") (class "Default")
      (node (ref "R27") (pin "2") (pinfunction "2_2") (pintype "passive"))
      (node (ref "R31") (pin "2") (pintype "passive"))
      (node (ref "U2") (pin "13") (pinfunction "DUPLEX_LED_/_PHYADDR0_STRAP_13") (pintype "bidirectional"))
    )
    (net (code "67") (name "Net-(U2A-TCK)") (class "Default")
      (node (ref "R18") (pin "1") (pintype "passive"))
      (node (ref "U2") (pin "24") (pinfunction "TCK_24") (pintype "bidirectional"))
      (node (ref "U2") (pin "27") (pinfunction "TMS_27") (pintype "bidirectional"))
      (node (ref "U2") (pin "31") (pinfunction "TDI_31") (pintype "bidirectional"))
      (node (ref "U2") (pin "32") (pinfunction "~{TRST}_32") (pintype "bidirectional"))
    )
    (net (code "68") (name "Net-(U2B-1V8_AVDD2)") (class "Default")
      (node (ref "C17") (pin "2") (pintype "passive"))
      (node (ref "C18") (pin "2") (pinfunction "2_2") (pintype "passive"))
      (node (ref "R8") (pin "1") (pinfunction "1_1") (pintype "passive"))
      (node (ref "U2") (pin "98") (pinfunction "1V8_AVDD2_98") (pintype "power_in"))
    )
    (net (code "69") (name "Net-(U2B-BG_REF)") (class "Default")
      (node (ref "R10") (pin "2") (pinfunction "2_2") (pintype "passive"))
      (node (ref "U2") (pin "102") (pinfunction "BG_REF_102") (pintype "input"))
    )
    (net (code "70") (name "VCC") (class "Default")
      (node (ref "C35") (pin "1") (pintype "passive"))
      (node (ref "C36") (pin "1") (pintype "passive"))
      (node (ref "C37") (pin "1") (pintype "passive"))
      (node (ref "C38") (pin "1") (pintype "passive"))
      (node (ref "C39") (pin "1") (pintype "passive"))
      (node (ref "C45") (pin "1") (pintype "passive"))
      (node (ref "R23") (pin "1") (pintype "passive"))
      (node (ref "R24") (pin "1") (pintype "passive"))
      (node (ref "R28") (pin "2") (pintype "passive"))
      (node (ref "R29") (pin "2") (pintype "passive"))
      (node (ref "R30") (pin "2") (pintype "passive"))
      (node (ref "R32") (pin "2") (pinfunction "2_2") (pintype "passive"))
      (node (ref "R33") (pin "2") (pinfunction "2_2") (pintype "passive"))
      (node (ref "R34") (pin "2") (pinfunction "2_2") (pintype "passive"))
      (node (ref "U2") (pin "15") (pinfunction "IO_VDD_15") (pintype "power_in"))
      (node (ref "U2") (pin "21") (pinfunction "IO_VDD_21") (pintype "power_in"))
      (node (ref "U2") (pin "29") (pinfunction "IO_VDD_29") (pintype "power_in"))
      (node (ref "U2") (pin "34") (pinfunction "VDD_SEL_STRAP_34") (pintype "bidirectional"))
      (node (ref "U2") (pin "37") (pinfunction "IO_VDD_37") (pintype "power_in"))
      (node (ref "U2") (pin "4") (pinfunction "IO_VDD_4") (pintype "power_in"))
      (node (ref "U2") (pin "42") (pinfunction "IO_VDD_42") (pintype "power_in"))
      (node (ref "U2") (pin "53") (pinfunction "IO_VDD_53") (pintype "power_in"))
      (node (ref "U2") (pin "58") (pinfunction "IO_VDD_58") (pintype "power_in"))
      (node (ref "U2") (pin "69") (pinfunction "IO_VDD_69") (pintype "power_in"))
      (node (ref "U2") (pin "77") (pinfunction "IO_VDD_77") (pintype "power_in"))
      (node (ref "U2") (pin "83") (pinfunction "IO_VDD_83") (pintype "power_in"))
      (node (ref "U2") (pin "90") (pinfunction "IO_VDD_90") (pintype "power_in"))
    )
    (net (code "71") (name "unconnected-(U2A-CLK_TO_MAC-Pad85)") (class "Default")
      (node (ref "U2") (pin "85") (pinfunction "CLK_TO_MAC_85") (pintype "output"))
    )
    (net (code "72") (name "unconnected-(U2A-MDIX_EN_STRAP-Pad89)") (class "Default")
      (node (ref "U2") (pin "89") (pinfunction "MDIX_EN_STRAP_89") (pintype "bidirectional"))
    )
    (net (code "73") (name "unconnected-(U2A-TDO-Pad28)") (class "Default")
      (node (ref "U2") (pin "28") (pinfunction "TDO_28") (pintype "bidirectional"))
    )
  )
)
